# powermeter_without_jack.net
KiCad netlist of a schematic drawn in EAGLE
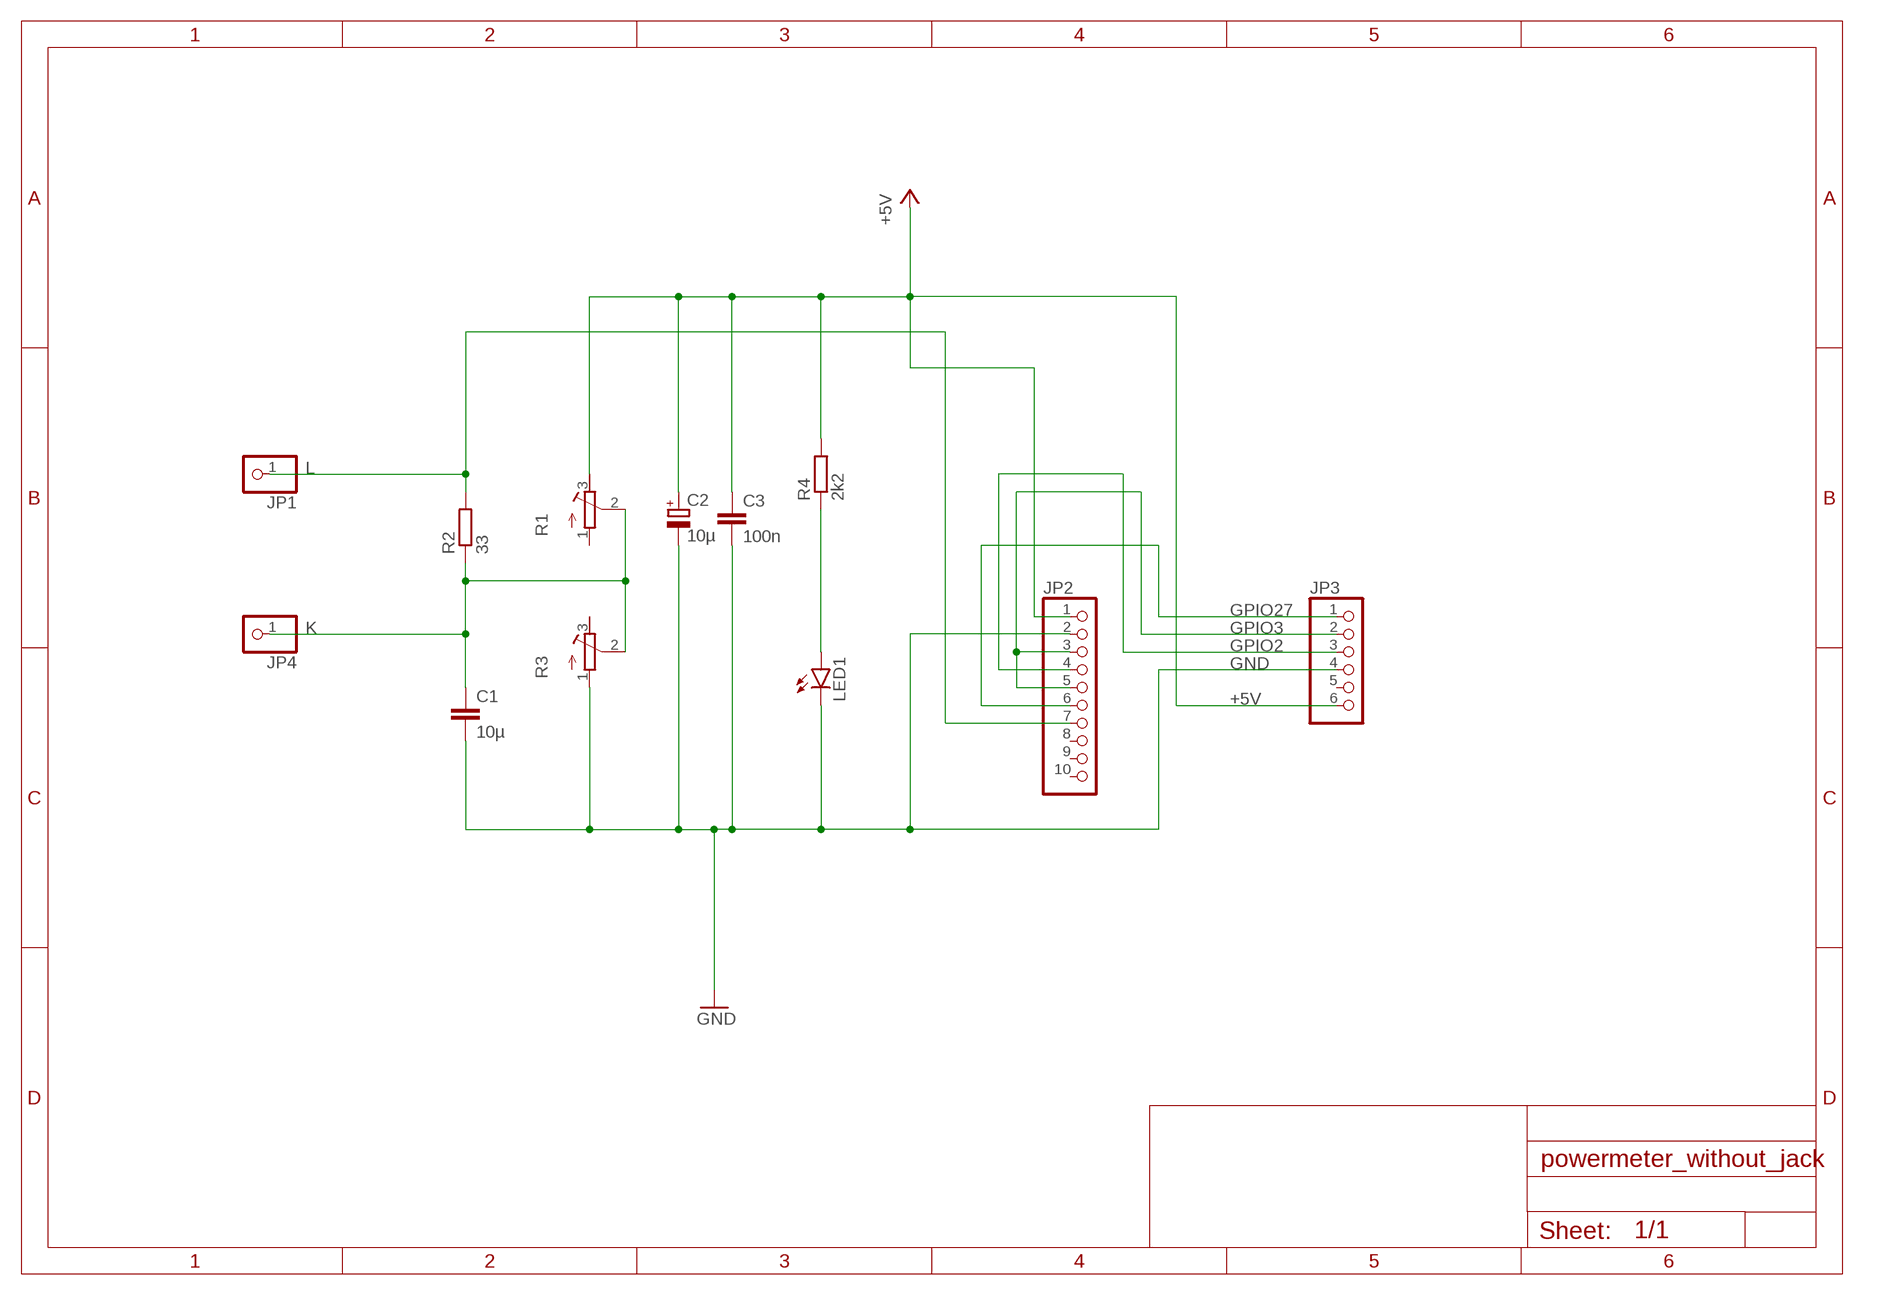
[diagram p0: schematic, sheet 1]

(export (version "E")
  (design (tool "Eeschema 10.0.6"))
  (components
    (comp (ref "C1")
      (value "10µ")
      (footprint "eagle-import:C075-052X106")
      (libsource (lib "eagle-import") (part "C-EU075-052X106"))
    )
    (comp (ref "C2")
      (value "10µ")
      (footprint "eagle-import:E5-5")
      (libsource (lib "eagle-import") (part "CPOL-EUE5-5"))
    )
    (comp (ref "C3")
      (value "100n")
      (footprint "eagle-import:C050-025X075")
      (libsource (lib "eagle-import") (part "C-EU050-025X075"))
    )
    (comp (ref "JP1")
      (value "PINHD-1X1")
      (footprint "eagle-import:1X01")
      (libsource (lib "eagle-import") (part "PINHD-1X1"))
    )
    (comp (ref "JP2")
      (value "PINHD-1X10")
      (footprint "eagle-import:1X10")
      (libsource (lib "eagle-import") (part "PINHD-1X10"))
    )
    (comp (ref "JP3")
      (value "PINHD-1X6")
      (footprint "eagle-import:1X06")
      (libsource (lib "eagle-import") (part "PINHD-1X6"))
    )
    (comp (ref "JP4")
      (value "PINHD-1X1")
      (footprint "eagle-import:1X01")
      (libsource (lib "eagle-import") (part "PINHD-1X1"))
    )
    (comp (ref "LED1")
      (value "LED3MM")
      (footprint "eagle-import:LED3MM")
      (libsource (lib "eagle-import") (part "LED3MM"))
    )
    (comp (ref "R1")
      (value "R-TRIMM3296W")
      (footprint "eagle-import:RTRIM3296W")
      (libsource (lib "eagle-import") (part "R-TRIMM3296W"))
    )
    (comp (ref "R2")
      (value "33")
      (footprint "eagle-import:0411_15")
      (libsource (lib "eagle-import") (part "R-EU_0411/15"))
    )
    (comp (ref "R3")
      (value "R-TRIMM3296W")
      (footprint "eagle-import:RTRIM3296W")
      (libsource (lib "eagle-import") (part "R-TRIMM3296W"))
    )
    (comp (ref "R4")
      (value "2k2")
      (footprint "eagle-import:0207_10")
      (libsource (lib "eagle-import") (part "R-EU_0207/10"))
    )
  )
  (nets
    (net (code "1") (name "+5V") (class "Default")
      (node (ref "C2") (pin "+") (pinfunction "+_+") (pintype "passive"))
      (node (ref "C3") (pin "1") (pinfunction "1_1") (pintype "passive"))
      (node (ref "JP2") (pin "1") (pinfunction "1_1") (pintype "passive"))
      (node (ref "JP3") (pin "6") (pinfunction "6_6") (pintype "passive"))
      (node (ref "R1") (pin "3") (pinfunction "E_3") (pintype "passive"))
      (node (ref "R4") (pin "2") (pinfunction "2_2") (pintype "passive"))
    )
    (net (code "2") (name "/GPIO2") (class "Default")
      (node (ref "JP2") (pin "4") (pinfunction "4_4") (pintype "passive"))
      (node (ref "JP3") (pin "3") (pinfunction "3_3") (pintype "passive"))
    )
    (net (code "3") (name "/GPIO3") (class "Default")
      (node (ref "JP2") (pin "3") (pinfunction "3_3") (pintype "passive"))
      (node (ref "JP2") (pin "5") (pinfunction "5_5") (pintype "passive"))
      (node (ref "JP3") (pin "2") (pinfunction "2_2") (pintype "passive"))
    )
    (net (code "4") (name "/GPIO27") (class "Default")
      (node (ref "JP2") (pin "6") (pinfunction "6_6") (pintype "passive"))
      (node (ref "JP3") (pin "1") (pinfunction "1_1") (pintype "passive"))
    )
    (net (code "5") (name "/K") (class "Default")
      (node (ref "C1") (pin "1") (pinfunction "1_1") (pintype "passive"))
      (node (ref "JP4") (pin "1") (pinfunction "1_1") (pintype "passive"))
      (node (ref "R1") (pin "2") (pinfunction "S_2") (pintype "passive"))
      (node (ref "R2") (pin "1") (pinfunction "1_1") (pintype "passive"))
      (node (ref "R3") (pin "2") (pinfunction "S_2") (pintype "passive"))
    )
    (net (code "6") (name "/L") (class "Default")
      (node (ref "JP1") (pin "1") (pinfunction "1_1") (pintype "passive"))
      (node (ref "JP2") (pin "7") (pinfunction "7_7") (pintype "passive"))
      (node (ref "R2") (pin "2") (pinfunction "2_2") (pintype "passive"))
    )
    (net (code "7") (name "GND") (class "Default")
      (node (ref "C1") (pin "2") (pinfunction "2_2") (pintype "passive"))
      (node (ref "C2") (pin "-") (pinfunction "-_-") (pintype "passive"))
      (node (ref "C3") (pin "2") (pinfunction "2_2") (pintype "passive"))
      (node (ref "JP2") (pin "2") (pinfunction "2_2") (pintype "passive"))
      (node (ref "JP3") (pin "4") (pinfunction "4_4") (pintype "passive"))
      (node (ref "LED1") (pin "K") (pinfunction "C_K") (pintype "passive"))
      (node (ref "R3") (pin "1") (pinfunction "A_1") (pintype "passive"))
    )
    (net (code "8") (name "Net-(LED1-PadA)") (class "Default")
      (node (ref "LED1") (pin "A") (pinfunction "A_A") (pintype "passive"))
      (node (ref "R4") (pin "1") (pinfunction "1_1") (pintype "passive"))
    )
    (net (code "9") (name "unconnected-(JP2-Pad8)") (class "Default")
      (node (ref "JP2") (pin "8") (pinfunction "8_8") (pintype "passive"))
    )
    (net (code "10") (name "unconnected-(JP2-Pad9)") (class "Default")
      (node (ref "JP2") (pin "9") (pinfunction "9_9") (pintype "passive"))
    )
    (net (code "11") (name "unconnected-(JP2-Pad10)") (class "Default")
      (node (ref "JP2") (pin "10") (pinfunction "10_10") (pintype "passive"))
    )
    (net (code "12") (name "unconnected-(JP3-Pad5)") (class "Default")
      (node (ref "JP3") (pin "5") (pinfunction "5_5") (pintype "passive"))
    )
    (net (code "13") (name "unconnected-(R1-A-Pad1)") (class "Default")
      (node (ref "R1") (pin "1") (pinfunction "A_1") (pintype "passive"))
    )
    (net (code "14") (name "unconnected-(R3-E-Pad3)") (class "Default")
      (node (ref "R3") (pin "3") (pinfunction "E_3") (pintype "passive"))
    )
  )
)
